# Controller_Rev_3.net
KiCad netlist of a schematic drawn in EAGLE
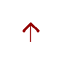
[diagram p0: schematic, sheet 1, part 1 of 3]
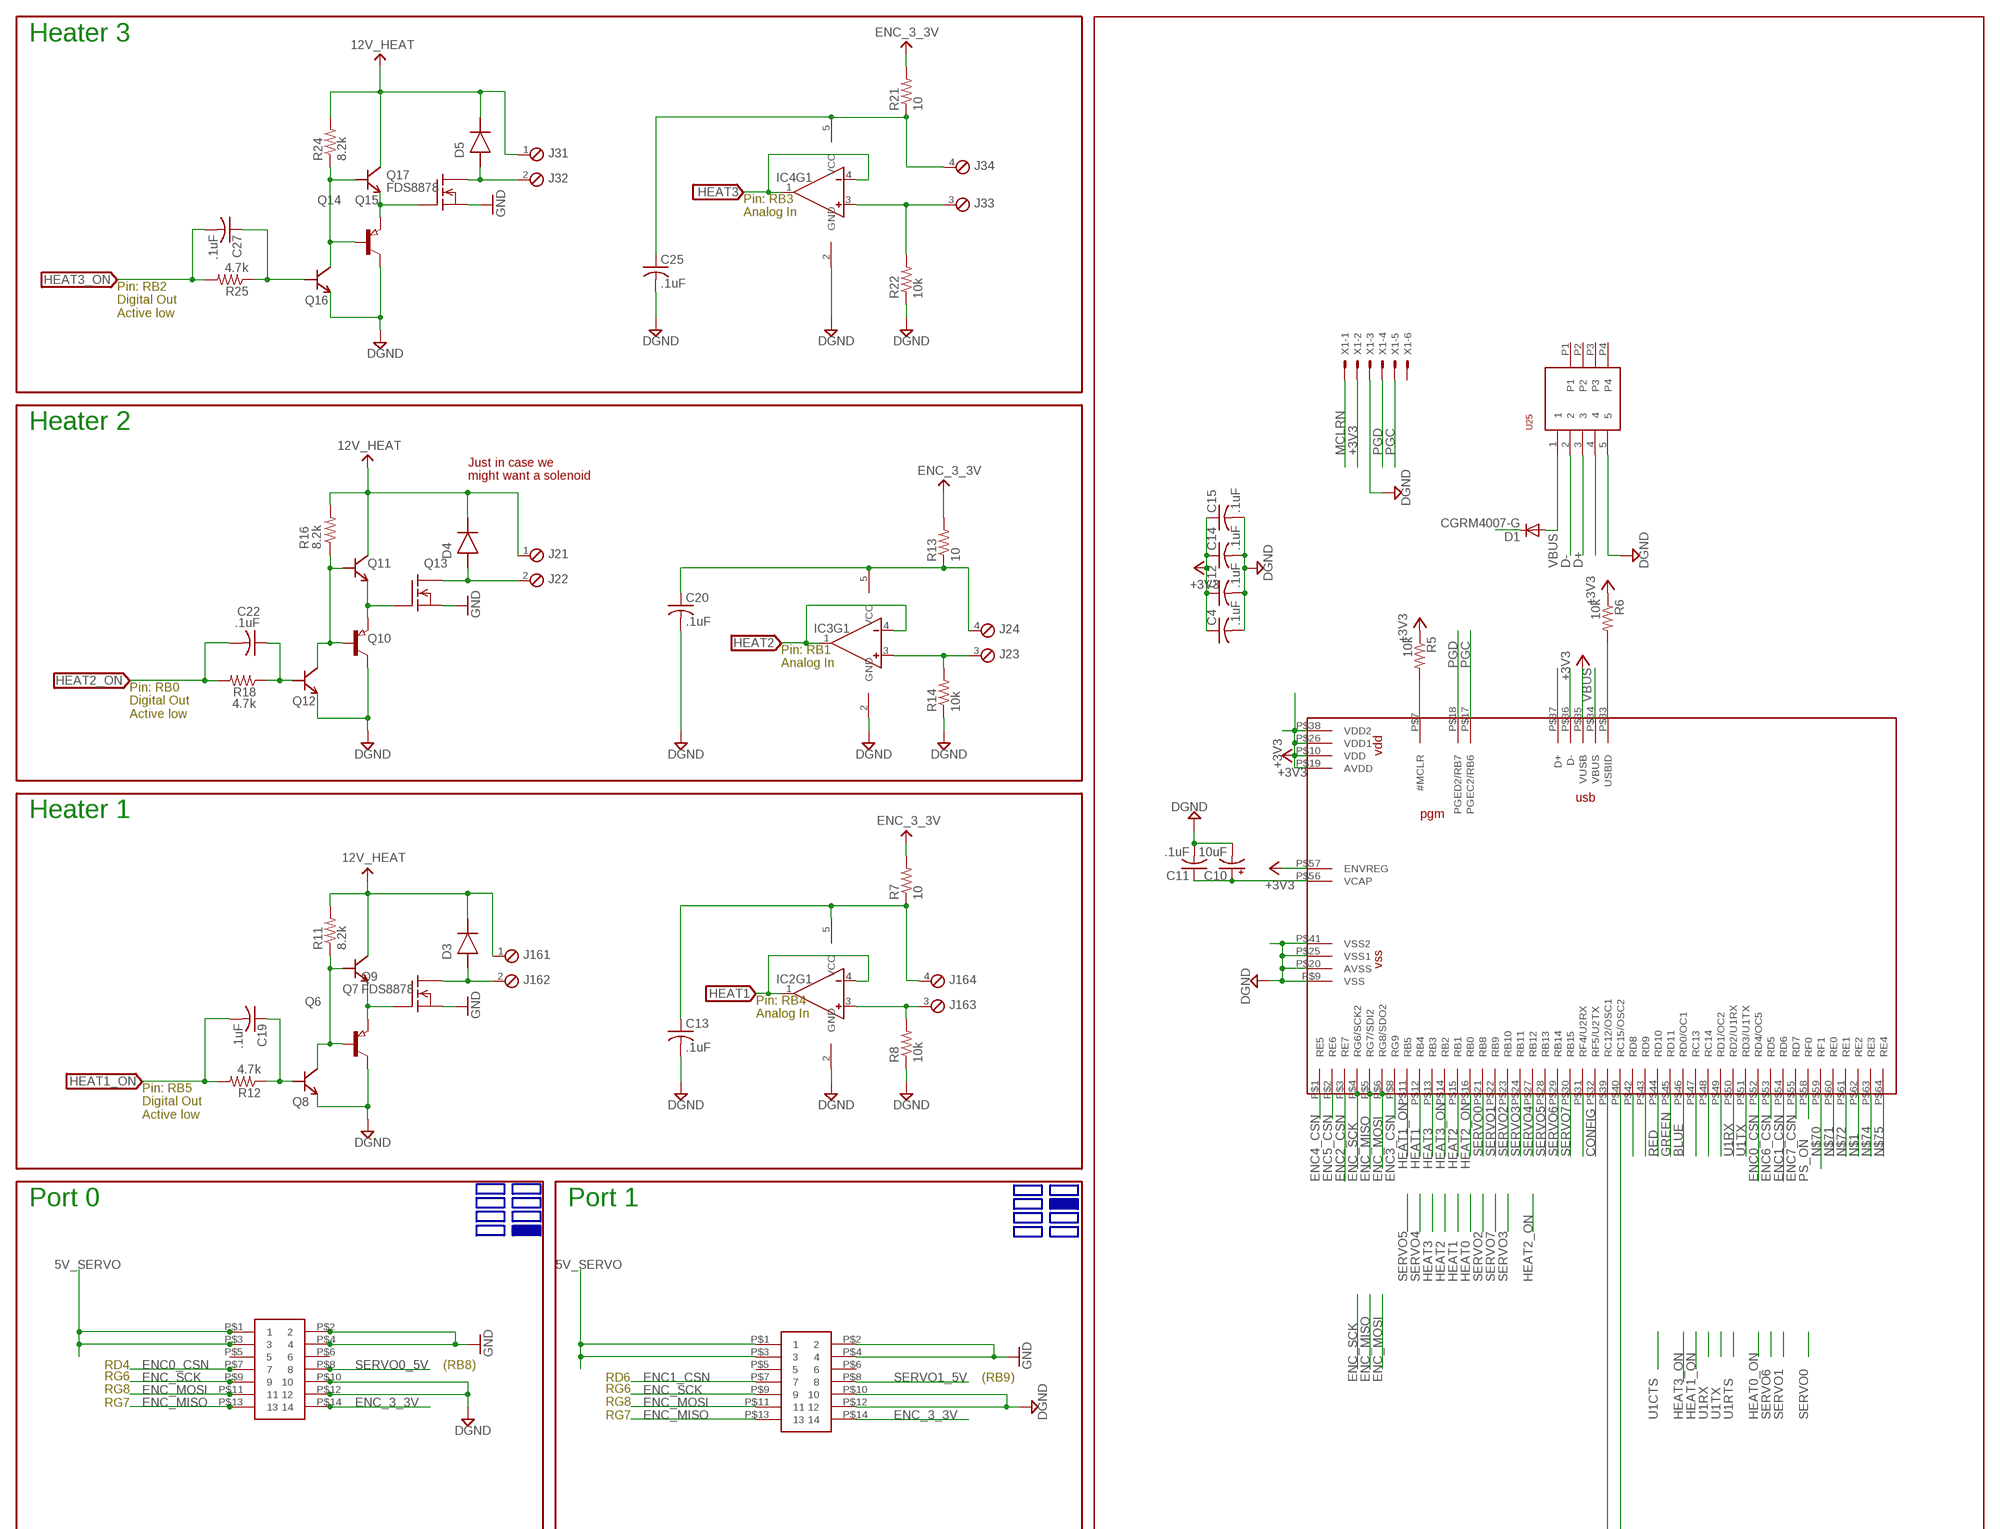
[diagram p1: schematic, sheet 1, part 2 of 3]
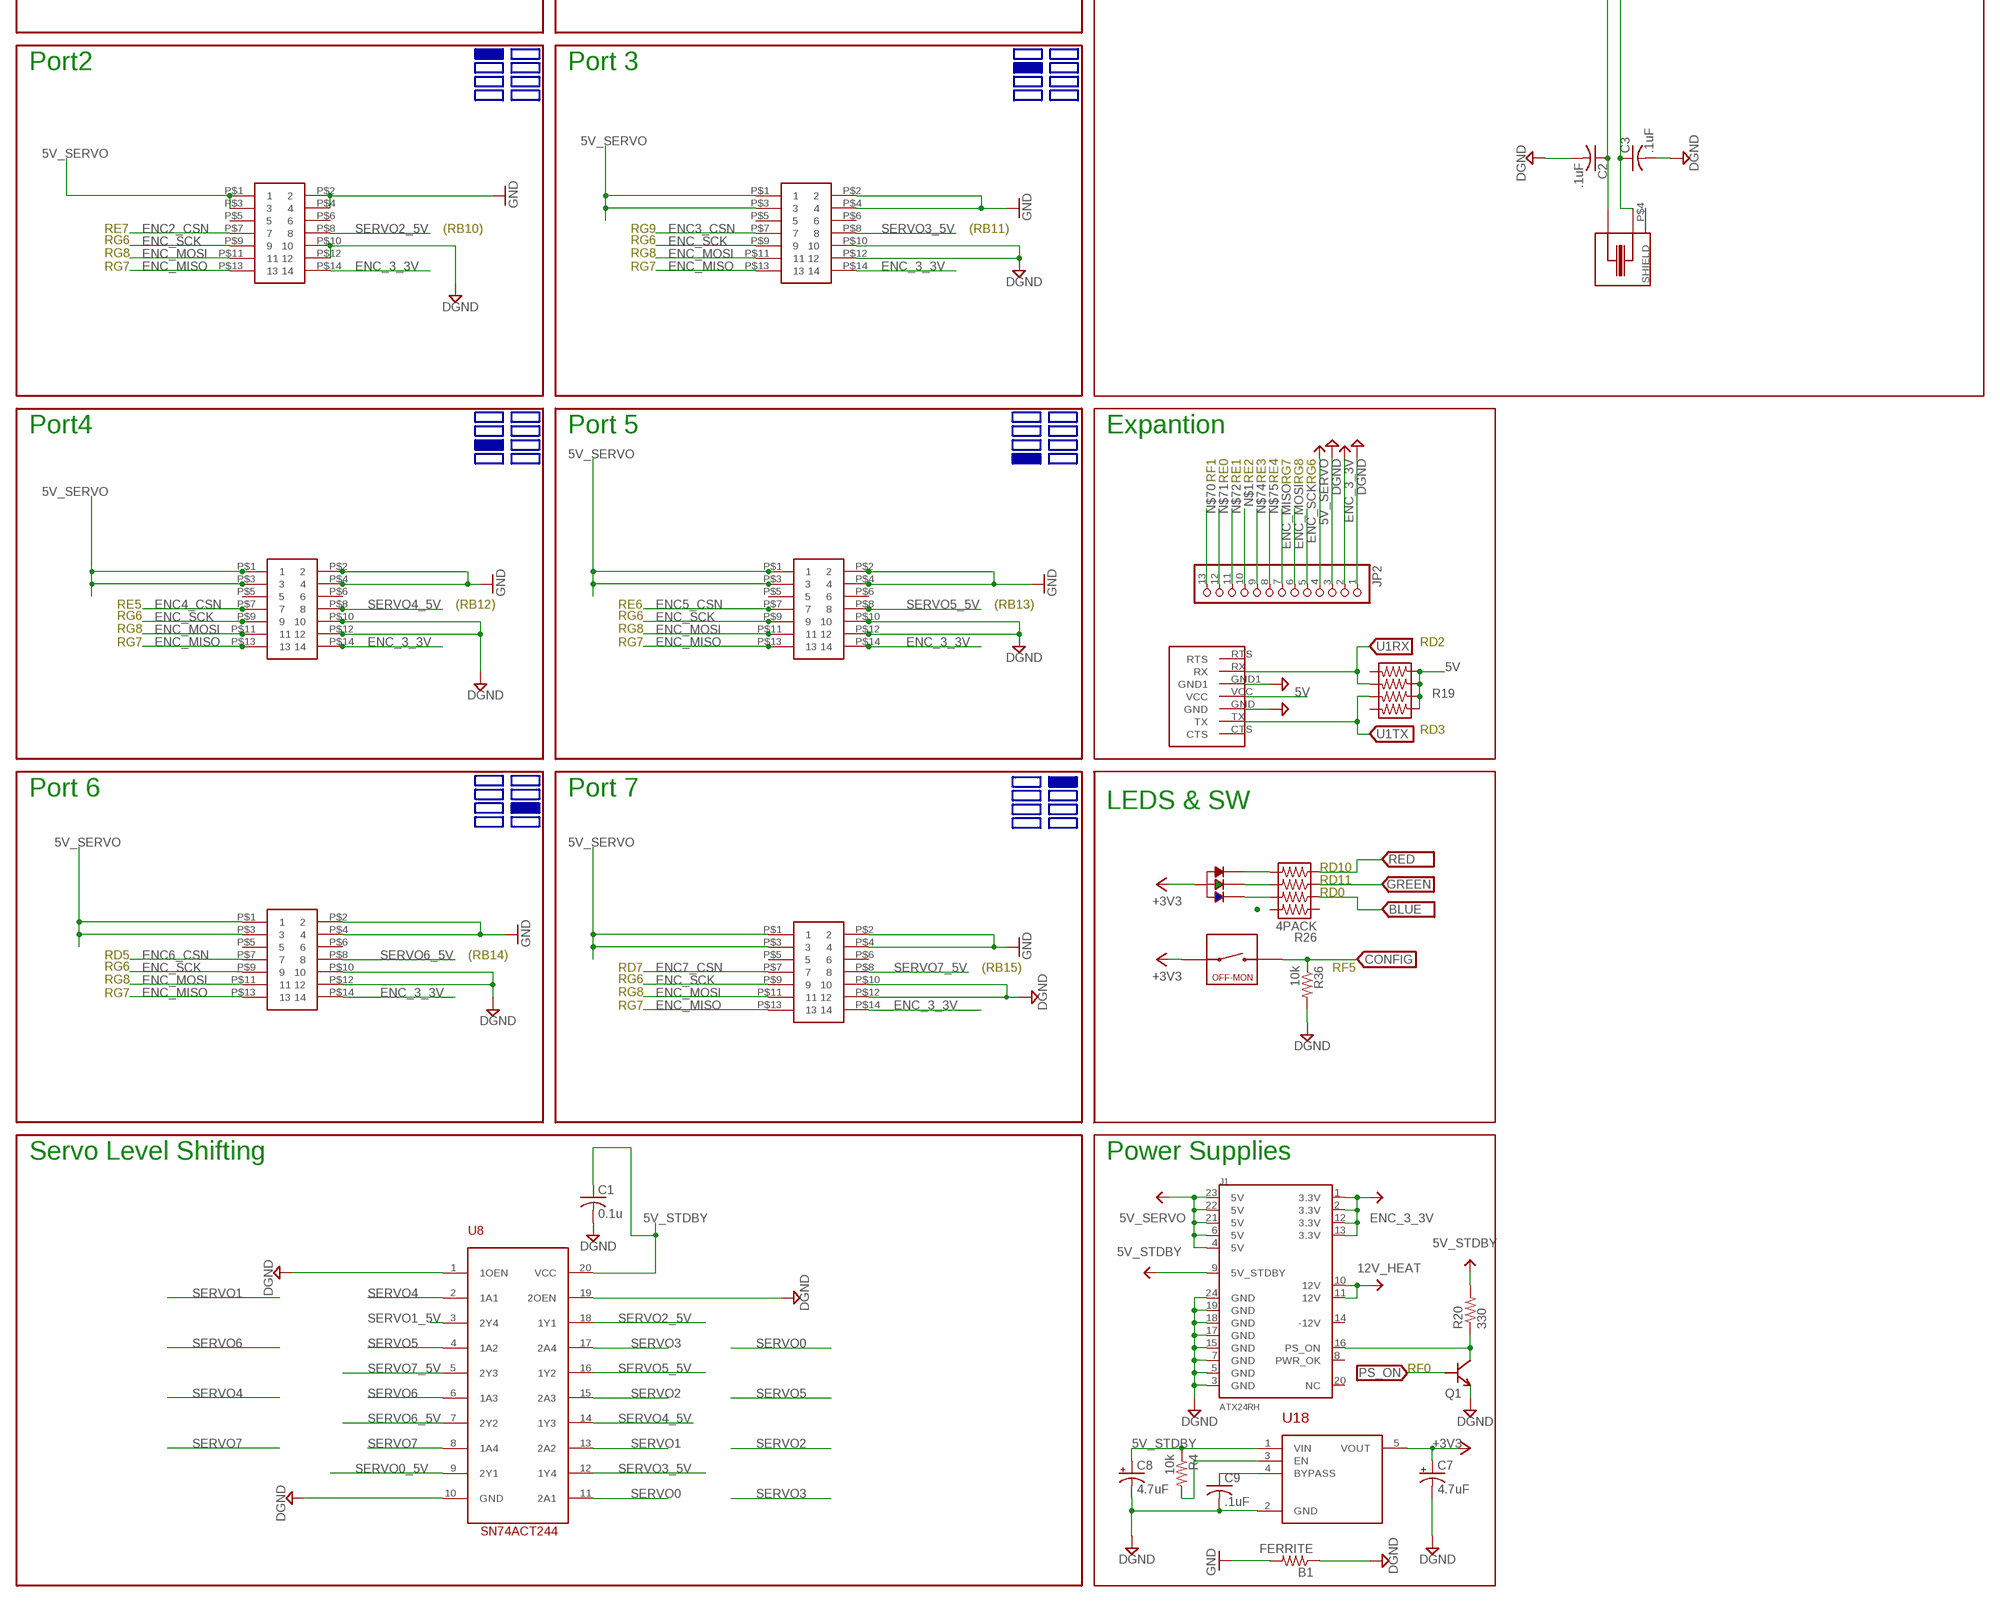
[diagram p2: schematic, sheet 1, part 3 of 3]

(export (version "E")
  (design (tool "Eeschema 10.0.6"))
  (components
    (comp (ref "B1")
      (value "FERRITE")
      (footprint "eagle-import:R0603")
      (libsource (lib "eagle-import") (part "R-US_R0603"))
    )
    (comp (ref "C1")
      (value "0.1u")
      (footprint "eagle-import:C0402")
      (libsource (lib "eagle-import") (part "resistor_C-USC0402"))
    )
    (comp (ref "C2")
      (value ".1uF")
      (footprint "eagle-import:C0603")
      (libsource (lib "eagle-import") (part "C-USC0603"))
    )
    (comp (ref "C3")
      (value ".1uF")
      (footprint "eagle-import:C0603")
      (libsource (lib "eagle-import") (part "C-USC0603"))
    )
    (comp (ref "C4")
      (value ".1uF")
      (footprint "eagle-import:C0603")
      (libsource (lib "eagle-import") (part "C-USC0603"))
    )
    (comp (ref "C7")
      (value "4.7uF")
      (footprint "eagle-import:R_2012-12R")
      (libsource (lib "eagle-import") (part "CPOL-USR/2012-12R"))
    )
    (comp (ref "C8")
      (value "4.7uF")
      (footprint "eagle-import:R_2012-12R")
      (libsource (lib "eagle-import") (part "CPOL-USR/2012-12R"))
    )
    (comp (ref "C9")
      (value ".1uF")
      (footprint "eagle-import:C0402")
      (libsource (lib "eagle-import") (part "C-USC0402"))
    )
    (comp (ref "C10")
      (value "10uF")
      (footprint "eagle-import:R_2012-12R")
      (libsource (lib "eagle-import") (part "CPOL-USR/2012-12R"))
    )
    (comp (ref "C11")
      (value ".1uF")
      (footprint "eagle-import:C0603")
      (libsource (lib "eagle-import") (part "C-USC0603"))
    )
    (comp (ref "C12")
      (value ".1uF")
      (footprint "eagle-import:C0603")
      (libsource (lib "eagle-import") (part "C-USC0603"))
    )
    (comp (ref "C13")
      (value ".1uF")
      (footprint "eagle-import:C0603")
      (libsource (lib "eagle-import") (part "C-USC0603"))
    )
    (comp (ref "C14")
      (value ".1uF")
      (footprint "eagle-import:C0603")
      (libsource (lib "eagle-import") (part "C-USC0603"))
    )
    (comp (ref "C15")
      (value ".1uF")
      (footprint "eagle-import:C0603")
      (libsource (lib "eagle-import") (part "C-USC0603"))
    )
    (comp (ref "C19")
      (value ".1uF")
      (footprint "eagle-import:C0603")
      (libsource (lib "eagle-import") (part "C-USC0603"))
    )
    (comp (ref "C20")
      (value ".1uF")
      (footprint "eagle-import:C0603")
      (libsource (lib "eagle-import") (part "C-USC0603"))
    )
    (comp (ref "C22")
      (value ".1uF")
      (footprint "eagle-import:C0603")
      (libsource (lib "eagle-import") (part "C-USC0603"))
    )
    (comp (ref "C25")
      (value ".1uF")
      (footprint "eagle-import:C0603")
      (libsource (lib "eagle-import") (part "C-USC0603"))
    )
    (comp (ref "C27")
      (value ".1uF")
      (footprint "eagle-import:C0603")
      (libsource (lib "eagle-import") (part "C-USC0603"))
    )
    (comp (ref "D1")
      (value "CGRM4007-G")
      (footprint "eagle-import:SOD-123_MINI-SMA")
      (libsource (lib "eagle-import") (part "CGRM400-G7"))
    )
    (comp (ref "D3")
      (value "DISCRETE_DIODESMA")
      (footprint "eagle-import:DISCRETE_SMA")
      (libsource (lib "eagle-import") (part "DISCRETE_DIODESMA"))
    )
    (comp (ref "D4")
      (value "DISCRETE_DIODESMA")
      (footprint "eagle-import:DISCRETE_SMA")
      (libsource (lib "eagle-import") (part "DISCRETE_DIODESMA"))
    )
    (comp (ref "D5")
      (value "DISCRETE_DIODESMA")
      (footprint "eagle-import:DISCRETE_SMA")
      (libsource (lib "eagle-import") (part "DISCRETE_DIODESMA"))
    )
    (comp (ref "IC2")
      (value "MICROCHIP_MCP6001-LT")
      (footprint "eagle-import:MICROCHIP_SC70-5-LT")
      (libsource (lib "eagle-import") (part "MICROCHIP_MCP6001-LT"))
    )
    (comp (ref "IC3")
      (value "MICROCHIP_MCP6001-LT")
      (footprint "eagle-import:MICROCHIP_SC70-5-LT")
      (libsource (lib "eagle-import") (part "MICROCHIP_MCP6001-LT"))
    )
    (comp (ref "IC4")
      (value "MICROCHIP_MCP6001-LT")
      (footprint "eagle-import:MICROCHIP_SC70-5-LT")
      (libsource (lib "eagle-import") (part "MICROCHIP_MCP6001-LT"))
    )
    (comp (ref "J1")
      (value "ATX24RH")
      (footprint "eagle-import:ATX24_RIGHT_ANGLE")
      (libsource (lib "eagle-import") (part "ATX24RH"))
    )
    (comp (ref "J2")
      (value "OSTVN04A150")
      (footprint "eagle-import:4POL254")
      (libsource (lib "eagle-import") (part "OSTVN04A150"))
    )
    (comp (ref "J3")
      (value "OSTVN04A150")
      (footprint "eagle-import:4POL254")
      (libsource (lib "eagle-import") (part "OSTVN04A150"))
    )
    (comp (ref "J10")
      (value "WASP7PIN")
      (footprint "eagle-import:WASP7PIN")
      (libsource (lib "eagle-import") (part "WASP7PIN"))
    )
    (comp (ref "J16")
      (value "OSTVN04A150")
      (footprint "eagle-import:4POL254")
      (libsource (lib "eagle-import") (part "OSTVN04A150"))
    )
    (comp (ref "JP2")
      (value "PINHD-1X13_BIG")
      (footprint "eagle-import:1X13-BIG")
      (libsource (lib "eagle-import") (part "PINHD-1X13_BIG"))
    )
    (comp (ref "Q1")
      (value "DISCRETE_MMBT3904LT1G")
      (footprint "eagle-import:DISCRETE_SOT23")
      (libsource (lib "eagle-import") (part "DISCRETE_MMBT3904LT1G"))
    )
    (comp (ref "Q6")
      (value "PNP-TRANSISTOR_SOT23")
      (footprint "eagle-import:SOT23")
      (libsource (lib "eagle-import") (part "PNP-TRANSISTOR_SOT23"))
    )
    (comp (ref "Q7")
      (value "DISCRETE_MMBT3904LT1G")
      (footprint "eagle-import:DISCRETE_SOT23")
      (libsource (lib "eagle-import") (part "DISCRETE_MMBT3904LT1G"))
    )
    (comp (ref "Q8")
      (value "DISCRETE_MMBT3904LT1G")
      (footprint "eagle-import:DISCRETE_SOT23")
      (libsource (lib "eagle-import") (part "DISCRETE_MMBT3904LT1G"))
    )
    (comp (ref "Q9")
      (value "FDS8878")
      (footprint "eagle-import:SO-8")
      (libsource (lib "eagle-import") (part "FDS5680"))
    )
    (comp (ref "Q10")
      (value "PNP-TRANSISTOR_SOT23")
      (footprint "eagle-import:SOT23")
      (libsource (lib "eagle-import") (part "PNP-TRANSISTOR_SOT23"))
    )
    (comp (ref "Q11")
      (value "DISCRETE_MMBT3904LT1G")
      (footprint "eagle-import:DISCRETE_SOT23")
      (libsource (lib "eagle-import") (part "DISCRETE_MMBT3904LT1G"))
    )
    (comp (ref "Q12")
      (value "DISCRETE_MMBT3904LT1G")
      (footprint "eagle-import:DISCRETE_SOT23")
      (libsource (lib "eagle-import") (part "DISCRETE_MMBT3904LT1G"))
    )
    (comp (ref "Q13")
      (value "FDS8878")
      (footprint "eagle-import:SO-8")
      (libsource (lib "eagle-import") (part "FDS5680"))
    )
    (comp (ref "Q14")
      (value "PNP-TRANSISTOR_SOT23")
      (footprint "eagle-import:SOT23")
      (libsource (lib "eagle-import") (part "PNP-TRANSISTOR_SOT23"))
    )
    (comp (ref "Q15")
      (value "DISCRETE_MMBT3904LT1G")
      (footprint "eagle-import:DISCRETE_SOT23")
      (libsource (lib "eagle-import") (part "DISCRETE_MMBT3904LT1G"))
    )
    (comp (ref "Q16")
      (value "DISCRETE_MMBT3904LT1G")
      (footprint "eagle-import:DISCRETE_SOT23")
      (libsource (lib "eagle-import") (part "DISCRETE_MMBT3904LT1G"))
    )
    (comp (ref "Q17")
      (value "FDS8878")
      (footprint "eagle-import:SO-8")
      (libsource (lib "eagle-import") (part "FDS5680"))
    )
    (comp (ref "R4")
      (value "10k")
      (footprint "eagle-import:R0402")
      (libsource (lib "eagle-import") (part "R-US_R0402"))
    )
    (comp (ref "R5")
      (value "10k")
      (footprint "eagle-import:R0603")
      (libsource (lib "eagle-import") (part "R-US_R0603"))
    )
    (comp (ref "R6")
      (value "10k")
      (footprint "eagle-import:R0603")
      (libsource (lib "eagle-import") (part "R-US_R0603"))
    )
    (comp (ref "R7")
      (value "10")
      (footprint "eagle-import:R0603")
      (libsource (lib "eagle-import") (part "R-US_R0603"))
    )
    (comp (ref "R8")
      (value "10k")
      (footprint "eagle-import:R0603")
      (libsource (lib "eagle-import") (part "R-US_R0603"))
    )
    (comp (ref "R11")
      (value "8.2k")
      (footprint "eagle-import:R0603")
      (libsource (lib "eagle-import") (part "R-US_R0603"))
    )
    (comp (ref "R12")
      (value "4.7k")
      (footprint "eagle-import:R0603")
      (libsource (lib "eagle-import") (part "R-US_R0603"))
    )
    (comp (ref "R13")
      (value "10")
      (footprint "eagle-import:R0603")
      (libsource (lib "eagle-import") (part "R-US_R0603"))
    )
    (comp (ref "R14")
      (value "10k")
      (footprint "eagle-import:R0603")
      (libsource (lib "eagle-import") (part "R-US_R0603"))
    )
    (comp (ref "R16")
      (value "8.2k")
      (footprint "eagle-import:R0603")
      (libsource (lib "eagle-import") (part "R-US_R0603"))
    )
    (comp (ref "R18")
      (value "4.7k")
      (footprint "eagle-import:R0603")
      (libsource (lib "eagle-import") (part "R-US_R0603"))
    )
    (comp (ref "R19")
      (value "4PACK")
      (footprint "eagle-import:4PACK_0603")
      (libsource (lib "eagle-import") (part "4PACK"))
    )
    (comp (ref "R20")
      (value "330")
      (footprint "eagle-import:R0603")
      (libsource (lib "eagle-import") (part "R-US_R0603"))
    )
    (comp (ref "R21")
      (value "10")
      (footprint "eagle-import:R0603")
      (libsource (lib "eagle-import") (part "R-US_R0603"))
    )
    (comp (ref "R22")
      (value "10k")
      (footprint "eagle-import:R0603")
      (libsource (lib "eagle-import") (part "R-US_R0603"))
    )
    (comp (ref "R24")
      (value "8.2k")
      (footprint "eagle-import:R0603")
      (libsource (lib "eagle-import") (part "R-US_R0603"))
    )
    (comp (ref "R25")
      (value "4.7k")
      (footprint "eagle-import:R0603")
      (libsource (lib "eagle-import") (part "R-US_R0603"))
    )
    (comp (ref "R26")
      (value "4PACK")
      (footprint "eagle-import:4PACK_0603")
      (libsource (lib "eagle-import") (part "4PACK"))
    )
    (comp (ref "R36")
      (value "10k")
      (footprint "eagle-import:R0603")
      (libsource (lib "eagle-import") (part "R-US_R0603"))
    )
    (comp (ref "SW3")
      (value "SPST")
      (footprint "eagle-import:B3U-1000P")
      (libsource (lib "eagle-import") (part "SPST"))
    )
    (comp (ref "U$1")
      (value "SBH11-NBPC-D07-SM-BK")
      (footprint "eagle-import:SBH11-NBPC-D07-SM-BK")
      (libsource (lib "eagle-import") (part "SBH11-NBPC-D07-SM-BK"))
    )
    (comp (ref "U$2")
      (value "SBH11-NBPC-D07-SM-BK")
      (footprint "eagle-import:SBH11-NBPC-D07-SM-BK")
      (libsource (lib "eagle-import") (part "SBH11-NBPC-D07-SM-BK"))
    )
    (comp (ref "U$3")
      (value "SBH11-NBPC-D07-SM-BK")
      (footprint "eagle-import:SBH11-NBPC-D07-SM-BK")
      (libsource (lib "eagle-import") (part "SBH11-NBPC-D07-SM-BK"))
    )
    (comp (ref "U$4")
      (value "SBH11-NBPC-D07-SM-BK")
      (footprint "eagle-import:SBH11-NBPC-D07-SM-BK")
      (libsource (lib "eagle-import") (part "SBH11-NBPC-D07-SM-BK"))
    )
    (comp (ref "U$5")
      (value "SBH11-NBPC-D07-SM-BK")
      (footprint "eagle-import:SBH11-NBPC-D07-SM-BK")
      (libsource (lib "eagle-import") (part "SBH11-NBPC-D07-SM-BK"))
    )
    (comp (ref "U$6")
      (value "SBH11-NBPC-D07-SM-BK")
      (footprint "eagle-import:SBH11-NBPC-D07-SM-BK")
      (libsource (lib "eagle-import") (part "SBH11-NBPC-D07-SM-BK"))
    )
    (comp (ref "U$7")
      (value "SBH11-NBPC-D07-SM-BK")
      (footprint "eagle-import:SBH11-NBPC-D07-SM-BK")
      (libsource (lib "eagle-import") (part "SBH11-NBPC-D07-SM-BK"))
    )
    (comp (ref "U$8")
      (value "SBH11-NBPC-D07-SM-BK")
      (footprint "eagle-import:SBH11-NBPC-D07-SM-BK")
      (libsource (lib "eagle-import") (part "SBH11-NBPC-D07-SM-BK"))
    )
    (comp (ref "U1")
      (value "TRI-LED-SMD")
      (footprint "eagle-import:TRI_LED_SMD")
      (libsource (lib "eagle-import") (part "TRI-LED-SMD"))
    )
    (comp (ref "U3")
      (value "PIC32-64TQFP64-2")
      (footprint "eagle-import:TQFP64-2")
      (libsource (lib "eagle-import") (part "PIC32-64TQFP64-2"))
    )
    (comp (ref "U8")
      (value "SN74ACT244")
      (footprint "eagle-import:20-SOIC")
      (libsource (lib "eagle-import") (part "SN74ACT244"))
    )
    (comp (ref "U18")
      (value "LDS3985XX33")
      (footprint "eagle-import:SOT23-5")
      (libsource (lib "eagle-import") (part "LDS3985XX33"))
    )
    (comp (ref "U25")
      (value "1734035-1_USB")
      (footprint "eagle-import:1734035-1_1734035")
      (libsource (lib "eagle-import") (part "1734035-1_USB"))
    )
    (comp (ref "X1")
      (value "22-23-2061")
      (footprint "eagle-import:22-23-2061")
      (fields (field (name "MF") "MOLEX"))
      (libsource (lib "eagle-import") (part "22-23-2061"))
    )
    (comp (ref "X2")
      (value "CMR3XXT")
      (footprint "eagle-import:CMR309T")
      (libsource (lib "eagle-import") (part "CMR3XXT"))
    )
  )
  (nets
    (net (code "2") (name "+3V3") (class "Default")
      (node (ref "C12") (pin "1") (pinfunction "1_1") (pintype "passive"))
      (node (ref "C14") (pin "1") (pinfunction "1_1") (pintype "passive"))
      (node (ref "C15") (pin "1") (pinfunction "1_1") (pintype "passive"))
      (node (ref "C4") (pin "1") (pinfunction "1_1") (pintype "passive"))
      (node (ref "C7") (pin "+") (pinfunction "+_+") (pintype "passive"))
      (node (ref "R5") (pin "1") (pinfunction "1_1") (pintype "passive"))
      (node (ref "R6") (pin "1") (pinfunction "1_1") (pintype "passive"))
      (node (ref "SW3") (pin "P$1") (pinfunction "P$1_P$1") (pintype "bidirectional"))
      (node (ref "U1") (pin "COMM-A") (pinfunction "COMM-A_COMM-A") (pintype "bidirectional"))
      (node (ref "U18") (pin "5") (pinfunction "VOUT_5") (pintype "bidirectional"))
      (node (ref "U3") (pin "P$10") (pinfunction "VDD_P$10") (pintype "bidirectional"))
      (node (ref "U3") (pin "P$19") (pinfunction "AVDD_P$19") (pintype "bidirectional"))
      (node (ref "U3") (pin "P$26") (pinfunction "VDD1_P$26") (pintype "bidirectional"))
      (node (ref "U3") (pin "P$35") (pinfunction "VUSB_P$35") (pintype "bidirectional"))
      (node (ref "U3") (pin "P$38") (pinfunction "VDD2_P$38") (pintype "bidirectional"))
      (node (ref "U3") (pin "P$57") (pinfunction "ENVREG_P$57") (pintype "bidirectional"))
      (node (ref "X1") (pin "2") (pinfunction "S_2") (pintype "passive"))
    )
    (net (code "3") (name "/5V") (class "Default")
      (node (ref "J10") (pin "VCC") (pinfunction "VCC_VCC") (pintype "bidirectional"))
      (node (ref "R19") (pin "R1B") (pinfunction "R1B_R1B") (pintype "passive"))
      (node (ref "R19") (pin "R2B") (pinfunction "R2B_R2B") (pintype "passive"))
      (node (ref "R19") (pin "R3B") (pinfunction "R3B_R3B") (pintype "passive"))
      (node (ref "R19") (pin "R4B") (pinfunction "R4B_R4B") (pintype "passive"))
    )
    (net (code "4") (name "/5V_SERVO") (class "Default")
      (node (ref "J1") (pin "21") (pinfunction "5V_21") (pintype "bidirectional"))
      (node (ref "J1") (pin "22") (pinfunction "5V_22") (pintype "bidirectional"))
      (node (ref "J1") (pin "23") (pinfunction "5V_23") (pintype "bidirectional"))
      (node (ref "J1") (pin "4") (pinfunction "5V_4") (pintype "bidirectional"))
      (node (ref "J1") (pin "6") (pinfunction "5V_6") (pintype "bidirectional"))
      (node (ref "JP2") (pin "4") (pinfunction "4_4") (pintype "passive"))
      (node (ref "U$1") (pin "P$1") (pinfunction "1_P$1") (pintype "bidirectional"))
      (node (ref "U$1") (pin "P$3") (pinfunction "3_P$3") (pintype "bidirectional"))
      (node (ref "U$2") (pin "P$1") (pinfunction "1_P$1") (pintype "bidirectional"))
      (node (ref "U$2") (pin "P$3") (pinfunction "3_P$3") (pintype "bidirectional"))
      (node (ref "U$3") (pin "P$1") (pinfunction "1_P$1") (pintype "bidirectional"))
      (node (ref "U$3") (pin "P$3") (pinfunction "3_P$3") (pintype "bidirectional"))
      (node (ref "U$4") (pin "P$1") (pinfunction "1_P$1") (pintype "bidirectional"))
      (node (ref "U$4") (pin "P$3") (pinfunction "3_P$3") (pintype "bidirectional"))
      (node (ref "U$5") (pin "P$1") (pinfunction "1_P$1") (pintype "bidirectional"))
      (node (ref "U$5") (pin "P$3") (pinfunction "3_P$3") (pintype "bidirectional"))
      (node (ref "U$6") (pin "P$1") (pinfunction "1_P$1") (pintype "bidirectional"))
      (node (ref "U$6") (pin "P$3") (pinfunction "3_P$3") (pintype "bidirectional"))
      (node (ref "U$7") (pin "P$1") (pinfunction "1_P$1") (pintype "bidirectional"))
      (node (ref "U$7") (pin "P$3") (pinfunction "3_P$3") (pintype "bidirectional"))
      (node (ref "U$8") (pin "P$1") (pinfunction "1_P$1") (pintype "bidirectional"))
      (node (ref "U$8") (pin "P$3") (pinfunction "3_P$3") (pintype "bidirectional"))
    )
    (net (code "5") (name "/5V_STDBY") (class "Default")
      (node (ref "C1") (pin "1") (pinfunction "1_1") (pintype "passive"))
      (node (ref "C8") (pin "+") (pinfunction "+_+") (pintype "passive"))
      (node (ref "D1") (pin "C") (pinfunction "C_C") (pintype "passive"))
      (node (ref "J1") (pin "9") (pinfunction "5V_STDBY_9") (pintype "bidirectional"))
      (node (ref "R20") (pin "2") (pinfunction "2_2") (pintype "passive"))
      (node (ref "R4") (pin "1") (pinfunction "1_1") (pintype "passive"))
      (node (ref "U18") (pin "1") (pinfunction "VIN_1") (pintype "bidirectional"))
      (node (ref "U8") (pin "20") (pinfunction "VCC_20") (pintype "bidirectional"))
    )
    (net (code "6") (name "/12V_HEAT") (class "Default")
      (node (ref "D3") (pin "C") (pinfunction "C_C") (pintype "bidirectional"))
      (node (ref "D4") (pin "C") (pinfunction "C_C") (pintype "bidirectional"))
      (node (ref "D5") (pin "C") (pinfunction "C_C") (pintype "bidirectional"))
      (node (ref "J1") (pin "10") (pinfunction "12V_10") (pintype "bidirectional"))
      (node (ref "J1") (pin "11") (pinfunction "12V_11") (pintype "bidirectional"))
      (node (ref "J16") (pin "1") (pinfunction "1_1") (pintype "passive"))
      (node (ref "J2") (pin "1") (pinfunction "1_1") (pintype "passive"))
      (node (ref "J3") (pin "1") (pinfunction "1_1") (pintype "passive"))
      (node (ref "Q11") (pin "3") (pinfunction "C_3") (pintype "bidirectional"))
      (node (ref "Q15") (pin "3") (pinfunction "C_3") (pintype "bidirectional"))
      (node (ref "Q7") (pin "3") (pinfunction "C_3") (pintype "bidirectional"))
      (node (ref "R11") (pin "2") (pinfunction "2_2") (pintype "passive"))
      (node (ref "R16") (pin "2") (pinfunction "2_2") (pintype "passive"))
      (node (ref "R24") (pin "2") (pinfunction "2_2") (pintype "passive"))
    )
    (net (code "7") (name "/BLUE") (class "Default")
      (node (ref "R26") (pin "R2B") (pinfunction "R2B_R2B") (pintype "passive"))
      (node (ref "U3") (pin "P$46") (pinfunction "RD0/OC1_P$46") (pintype "bidirectional"))
    )
    (net (code "8") (name "/CONFIG") (class "Default")
      (node (ref "R36") (pin "1") (pinfunction "1_1") (pintype "passive"))
      (node (ref "SW3") (pin "P$3") (pinfunction "P$2_P$3") (pintype "bidirectional"))
      (node (ref "U3") (pin "P$32") (pinfunction "RF5/U2TX_P$32") (pintype "bidirectional"))
    )
    (net (code "9") (name "/D+") (class "Default")
      (node (ref "U25") (pin "3") (pinfunction "3_3") (pintype "bidirectional"))
      (node (ref "U3") (pin "P$37") (pinfunction "D+_P$37") (pintype "bidirectional"))
    )
    (net (code "10") (name "/D-") (class "Default")
      (node (ref "U25") (pin "2") (pinfunction "2_2") (pintype "bidirectional"))
      (node (ref "U3") (pin "P$36") (pinfunction "D-_P$36") (pintype "bidirectional"))
    )
    (net (code "11") (name "/ENC0_CSN") (class "Default")
      (node (ref "U$8") (pin "P$7") (pinfunction "7_P$7") (pintype "bidirectional"))
      (node (ref "U3") (pin "P$52") (pinfunction "RD4/OC5_P$52") (pintype "bidirectional"))
    )
    (net (code "12") (name "/ENC1_CSN") (class "Default")
      (node (ref "U$6") (pin "P$7") (pinfunction "7_P$7") (pintype "bidirectional"))
      (node (ref "U3") (pin "P$54") (pinfunction "RD6_P$54") (pintype "bidirectional"))
    )
    (net (code "13") (name "/ENC2_CSN") (class "Default")
      (node (ref "U$1") (pin "P$7") (pinfunction "7_P$7") (pintype "bidirectional"))
      (node (ref "U3") (pin "P$3") (pinfunction "RE7_P$3") (pintype "bidirectional"))
    )
    (net (code "14") (name "/ENC3_CSN") (class "Default")
      (node (ref "U$2") (pin "P$7") (pinfunction "7_P$7") (pintype "bidirectional"))
      (node (ref "U3") (pin "P$8") (pinfunction "RG9_P$8") (pintype "bidirectional"))
    )
    (net (code "15") (name "/ENC4_CSN") (class "Default")
      (node (ref "U$3") (pin "P$7") (pinfunction "7_P$7") (pintype "bidirectional"))
      (node (ref "U3") (pin "P$1") (pinfunction "RE5_P$1") (pintype "bidirectional"))
    )
    (net (code "16") (name "/ENC5_CSN") (class "Default")
      (node (ref "U$4") (pin "P$7") (pinfunction "7_P$7") (pintype "bidirectional"))
      (node (ref "U3") (pin "P$2") (pinfunction "RE6_P$2") (pintype "bidirectional"))
    )
    (net (code "17") (name "/ENC6_CSN") (class "Default")
      (node (ref "U$7") (pin "P$7") (pinfunction "7_P$7") (pintype "bidirectional"))
      (node (ref "U3") (pin "P$53") (pinfunction "RD5_P$53") (pintype "bidirectional"))
    )
    (net (code "18") (name "/ENC7_CSN") (class "Default")
      (node (ref "U$5") (pin "P$7") (pinfunction "7_P$7") (pintype "bidirectional"))
      (node (ref "U3") (pin "P$55") (pinfunction "RD7_P$55") (pintype "bidirectional"))
    )
    (net (code "19") (name "/ENC_3_3V") (class "Default")
      (node (ref "J1") (pin "1") (pinfunction "3.3V_1") (pintype "bidirectional"))
      (node (ref "J1") (pin "12") (pinfunction "3.3V_12") (pintype "bidirectional"))
      (node (ref "J1") (pin "13") (pinfunction "3.3V_13") (pintype "bidirectional"))
      (node (ref "J1") (pin "2") (pinfunction "3.3V_2") (pintype "bidirectional"))
      (node (ref "JP2") (pin "2") (pinfunction "2_2") (pintype "passive"))
      (node (ref "R13") (pin "2") (pinfunction "2_2") (pintype "passive"))
      (node (ref "R21") (pin "2") (pinfunction "2_2") (pintype "passive"))
      (node (ref "R7") (pin "2") (pinfunction "2_2") (pintype "passive"))
      (node (ref "U$1") (pin "P$14") (pinfunction "14_P$14") (pintype "bidirectional"))
      (node (ref "U$2") (pin "P$14") (pinfunction "14_P$14") (pintype "bidirectional"))
      (node (ref "U$3") (pin "P$14") (pinfunction "14_P$14") (pintype "bidirectional"))
      (node (ref "U$4") (pin "P$14") (pinfunction "14_P$14") (pintype "bidirectional"))
      (node (ref "U$5") (pin "P$14") (pinfunction "14_P$14") (pintype "bidirectional"))
      (node (ref "U$6") (pin "P$14") (pinfunction "14_P$14") (pintype "bidirectional"))
      (node (ref "U$7") (pin "P$14") (pinfunction "14_P$14") (pintype "bidirectional"))
      (node (ref "U$8") (pin "P$14") (pinfunction "14_P$14") (pintype "bidirectional"))
    )
    (net (code "20") (name "/ENC_MISO") (class "Default")
      (node (ref "JP2") (pin "7") (pinfunction "7_7") (pintype "passive"))
      (node (ref "U$1") (pin "P$13") (pinfunction "13_P$13") (pintype "bidirectional"))
      (node (ref "U$2") (pin "P$13") (pinfunction "13_P$13") (pintype "bidirectional"))
      (node (ref "U$3") (pin "P$13") (pinfunction "13_P$13") (pintype "bidirectional"))
      (node (ref "U$4") (pin "P$13") (pinfunction "13_P$13") (pintype "bidirectional"))
      (node (ref "U$5") (pin "P$13") (pinfunction "13_P$13") (pintype "bidirectional"))
      (node (ref "U$6") (pin "P$13") (pinfunction "13_P$13") (pintype "bidirectional"))
      (node (ref "U$7") (pin "P$13") (pinfunction "13_P$13") (pintype "bidirectional"))
      (node (ref "U$8") (pin "P$13") (pinfunction "13_P$13") (pintype "bidirectional"))
      (node (ref "U3") (pin "P$5") (pinfunction "RG7/SDI2_P$5") (pintype "bidirectional"))
    )
    (net (code "21") (name "/ENC_MOSI") (class "Default")
      (node (ref "JP2") (pin "6") (pinfunction "6_6") (pintype "passive"))
      (node (ref "U$1") (pin "P$11") (pinfunction "11_P$11") (pintype "bidirectional"))
      (node (ref "U$2") (pin "P$11") (pinfunction "11_P$11") (pintype "bidirectional"))
      (node (ref "U$3") (pin "P$11") (pinfunction "11_P$11") (pintype "bidirectional"))
      (node (ref "U$4") (pin "P$11") (pinfunction "11_P$11") (pintype "bidirectional"))
      (node (ref "U$5") (pin "P$11") (pinfunction "11_P$11") (pintype "bidirectional"))
      (node (ref "U$6") (pin "P$11") (pinfunction "11_P$11") (pintype "bidirectional"))
      (node (ref "U$7") (pin "P$11") (pinfunction "11_P$11") (pintype "bidirectional"))
      (node (ref "U$8") (pin "P$11") (pinfunction "11_P$11") (pintype "bidirectional"))
      (node (ref "U3") (pin "P$6") (pinfunction "RG8/SDO2_P$6") (pintype "bidirectional"))
    )
    (net (code "22") (name "/ENC_SCK") (class "Default")
      (node (ref "JP2") (pin "5") (pinfunction "5_5") (pintype "passive"))
      (node (ref "U$1") (pin "P$9") (pinfunction "9_P$9") (pintype "bidirectional"))
      (node (ref "U$2") (pin "P$9") (pinfunction "9_P$9") (pintype "bidirectional"))
      (node (ref "U$3") (pin "P$9") (pinfunction "9_P$9") (pintype "bidirectional"))
      (node (ref "U$4") (pin "P$9") (pinfunction "9_P$9") (pintype "bidirectional"))
      (node (ref "U$5") (pin "P$9") (pinfunction "9_P$9") (pintype "bidirectional"))
      (node (ref "U$6") (pin "P$9") (pinfunction "9_P$9") (pintype "bidirectional"))
      (node (ref "U$7") (pin "P$9") (pinfunction "9_P$9") (pintype "bidirectional"))
      (node (ref "U$8") (pin "P$9") (pinfunction "9_P$9") (pintype "bidirectional"))
      (node (ref "U3") (pin "P$4") (pinfunction "RG6/SCK2_P$4") (pintype "bidirectional"))
    )
    (net (code "23") (name "/GREEN") (class "Default")
      (node (ref "R26") (pin "R3B") (pinfunction "R3B_R3B") (pintype "passive"))
      (node (ref "U3") (pin "P$45") (pinfunction "RD11_P$45") (pintype "bidirectional"))
    )
    (net (code "26") (name "/HEAT1") (class "Default")
      (node (ref "IC2") (pin "1") (pinfunction "OUT_1") (pintype "output"))
      (node (ref "IC2") (pin "4") (pinfunction "IN-_4") (pintype "input"))
      (node (ref "U3") (pin "P$12") (pinfunction "RB4_P$12") (pintype "bidirectional"))
    )
    (net (code "27") (name "/HEAT1_ON") (class "Default")
      (node (ref "C19") (pin "2") (pinfunction "2_2") (pintype "passive"))
      (node (ref "R12") (pin "2") (pinfunction "2_2") (pintype "passive"))
      (node (ref "U3") (pin "P$11") (pinfunction "RB5_P$11") (pintype "bidirectional"))
    )
    (net (code "28") (name "/HEAT2") (class "Default")
      (node (ref "IC3") (pin "1") (pinfunction "OUT_1") (pintype "output"))
      (node (ref "IC3") (pin "4") (pinfunction "IN-_4") (pintype "input"))
      (node (ref "U3") (pin "P$15") (pinfunction "RB1_P$15") (pintype "bidirectional"))
    )
    (net (code "29") (name "/HEAT2_ON") (class "Default")
      (node (ref "C22") (pin "2") (pinfunction "2_2") (pintype "passive"))
      (node (ref "R18") (pin "2") (pinfunction "2_2") (pintype "passive"))
      (node (ref "U3") (pin "P$16") (pinfunction "RB0_P$16") (pintype "bidirectional"))
    )
    (net (code "30") (name "/HEAT3") (class "Default")
      (node (ref "IC4") (pin "1") (pinfunction "OUT_1") (pintype "output"))
      (node (ref "IC4") (pin "4") (pinfunction "IN-_4") (pintype "input"))
      (node (ref "U3") (pin "P$13") (pinfunction "RB3_P$13") (pintype "bidirectional"))
    )
    (net (code "31") (name "/HEAT3_ON") (class "Default")
      (node (ref "C27") (pin "2") (pinfunction "2_2") (pintype "passive"))
      (node (ref "R25") (pin "2") (pinfunction "2_2") (pintype "passive"))
      (node (ref "U3") (pin "P$14") (pinfunction "RB2_P$14") (pintype "bidirectional"))
    )
    (net (code "32") (name "/MCLRN") (class "Default")
      (node (ref "R5") (pin "2") (pinfunction "2_2") (pintype "passive"))
      (node (ref "U3") (pin "P$7") (pinfunction "#MCLR_P$7") (pintype "bidirectional"))
      (node (ref "X1") (pin "1") (pinfunction "S_1") (pintype "passive"))
    )
    (net (code "33") (name "/N$1") (class "Default")
      (node (ref "JP2") (pin "10") (pinfunction "10_10") (pintype "passive"))
      (node (ref "U3") (pin "P$62") (pinfunction "RE2_P$62") (pintype "bidirectional"))
    )
    (net (code "34") (name "/N$70") (class "Default")
      (node (ref "JP2") (pin "13") (pinfunction "13_13") (pintype "passive"))
      (node (ref "U3") (pin "P$59") (pinfunction "RF1_P$59") (pintype "bidirectional"))
    )
    (net (code "35") (name "/N$71") (class "Default")
      (node (ref "JP2") (pin "12") (pinfunction "12_12") (pintype "passive"))
      (node (ref "U3") (pin "P$60") (pinfunction "RE0_P$60") (pintype "bidirectional"))
    )
    (net (code "36") (name "/N$72") (class "Default")
      (node (ref "JP2") (pin "11") (pinfunction "11_11") (pintype "passive"))
      (node (ref "U3") (pin "P$61") (pinfunction "RE1_P$61") (pintype "bidirectional"))
    )
    (net (code "37") (name "/N$74") (class "Default")
      (node (ref "JP2") (pin "9") (pinfunction "9_9") (pintype "passive"))
      (node (ref "U3") (pin "P$63") (pinfunction "RE3_P$63") (pintype "bidirectional"))
    )
    (net (code "38") (name "/N$75") (class "Default")
      (node (ref "JP2") (pin "8") (pinfunction "8_8") (pintype "passive"))
      (node (ref "U3") (pin "P$64") (pinfunction "RE4_P$64") (pintype "bidirectional"))
    )
    (net (code "39") (name "/PGC") (class "Default")
      (node (ref "U3") (pin "P$17") (pinfunction "PGEC2/RB6_P$17") (pintype "bidirectional"))
      (node (ref "X1") (pin "5") (pinfunction "S_5") (pintype "passive"))
    )
    (net (code "40") (name "/PGD") (class "Default")
      (node (ref "U3") (pin "P$18") (pinfunction "PGED2/RB7_P$18") (pintype "bidirectional"))
      (node (ref "X1") (pin "4") (pinfunction "S_4") (pintype "passive"))
    )
    (net (code "41") (name "/PS_ON") (class "Default")
      (node (ref "Q1") (pin "1") (pinfunction "B_1") (pintype "bidirectional"))
      (node (ref "U3") (pin "P$58") (pinfunction "RF0_P$58") (pintype "bidirectional"))
    )
    (net (code "42") (name "/RED") (class "Default")
      (node (ref "R26") (pin "R4B") (pinfunction "R4B_R4B") (pintype "passive"))
      (node (ref "U3") (pin "P$44") (pinfunction "RD10_P$44") (pintype "bidirectional"))
    )
    (net (code "43") (name "/SERVO0") (class "Default")
      (node (ref "U3") (pin "P$21") (pinfunction "RB8_P$21") (pintype "bidirectional"))
      (node (ref "U8") (pin "11") (pinfunction "2A1_11") (pintype "bidirectional"))
    )
    (net (code "44") (name "/SERVO0_5V") (class "Default")
      (node (ref "U$8") (pin "P$8") (pinfunction "8_P$8") (pintype "bidirectional"))
      (node (ref "U8") (pin "9") (pinfunction "2Y1_9") (pintype "bidirectional"))
    )
    (net (code "45") (name "/SERVO1") (class "Default")
      (node (ref "U3") (pin "P$22") (pinfunction "RB9_P$22") (pintype "bidirectional"))
      (node (ref "U8") (pin "13") (pinfunction "2A2_13") (pintype "bidirectional"))
    )
    (net (code "46") (name "/SERVO1_5V") (class "Default")
      (node (ref "U$6") (pin "P$8") (pinfunction "8_P$8") (pintype "bidirectional"))
      (node (ref "U8") (pin "3") (pinfunction "2Y4_3") (pintype "bidirectional"))
    )
    (net (code "47") (name "/SERVO2") (class "Default")
      (node (ref "U3") (pin "P$23") (pinfunction "RB10_P$23") (pintype "bidirectional"))
      (node (ref "U8") (pin "15") (pinfunction "2A3_15") (pintype "bidirectional"))
    )
    (net (code "48") (name "/SERVO2_5V") (class "Default")
      (node (ref "U$1") (pin "P$8") (pinfunction "8_P$8") (pintype "bidirectional"))
      (node (ref "U8") (pin "18") (pinfunction "1Y1_18") (pintype "bidirectional"))
    )
    (net (code "49") (name "/SERVO3") (class "Default")
      (node (ref "U3") (pin "P$24") (pinfunction "RB11_P$24") (pintype "bidirectional"))
      (node (ref "U8") (pin "17") (pinfunction "2A4_17") (pintype "bidirectional"))
    )
    (net (code "50") (name "/SERVO3_5V") (class "Default")
      (node (ref "U$2") (pin "P$8") (pinfunction "8_P$8") (pintype "bidirectional"))
      (node (ref "U8") (pin "12") (pinfunction "1Y4_12") (pintype "bidirectional"))
    )
    (net (code "51") (name "/SERVO4") (class "Default")
      (node (ref "U3") (pin "P$27") (pinfunction "RB12_P$27") (pintype "bidirectional"))
      (node (ref "U8") (pin "2") (pinfunction "1A1_2") (pintype "bidirectional"))
    )
    (net (code "52") (name "/SERVO4_5V") (class "Default")
      (node (ref "U$3") (pin "P$8") (pinfunction "8_P$8") (pintype "bidirectional"))
      (node (ref "U8") (pin "14") (pinfunction "1Y3_14") (pintype "bidirectional"))
    )
    (net (code "53") (name "/SERVO5") (class "Default")
      (node (ref "U3") (pin "P$28") (pinfunction "RB13_P$28") (pintype "bidirectional"))
      (node (ref "U8") (pin "4") (pinfunction "1A2_4") (pintype "bidirectional"))
    )
    (net (code "54") (name "/SERVO5_5V") (class "Default")
      (node (ref "U$4") (pin "P$8") (pinfunction "8_P$8") (pintype "bidirectional"))
      (node (ref "U8") (pin "16") (pinfunction "1Y2_16") (pintype "bidirectional"))
    )
    (net (code "55") (name "/SERVO6") (class "Default")
      (node (ref "U3") (pin "P$29") (pinfunction "RB14_P$29") (pintype "bidirectional"))
      (node (ref "U8") (pin "6") (pinfunction "1A3_6") (pintype "bidirectional"))
    )
    (net (code "56") (name "/SERVO6_5V") (class "Default")
      (node (ref "U$7") (pin "P$8") (pinfunction "8_P$8") (pintype "bidirectional"))
      (node (ref "U8") (pin "7") (pinfunction "2Y2_7") (pintype "bidirectional"))
    )
    (net (code "57") (name "/SERVO7") (class "Default")
      (node (ref "U3") (pin "P$30") (pinfunction "RB15_P$30") (pintype "bidirectional"))
      (node (ref "U8") (pin "8") (pinfunction "1A4_8") (pintype "bidirectional"))
    )
    (net (code "58") (name "/SERVO7_5V") (class "Default")
      (node (ref "U$5") (pin "P$8") (pinfunction "8_P$8") (pintype "bidirectional"))
      (node (ref "U8") (pin "5") (pinfunction "2Y3_5") (pintype "bidirectional"))
    )
    (net (code "61") (name "/U1RX") (class "Default")
      (node (ref "J10") (pin "RX") (pinfunction "RX_RX") (pintype "bidirectional"))
      (node (ref "R19") (pin "R2A") (pinfunction "R2A_R2A") (pintype "passive"))
      (node (ref "U3") (pin "P$50") (pinfunction "RD2/U1RX_P$50") (pintype "bidirectional"))
    )
    (net (code "62") (name "/U1TX") (class "Default")
      (node (ref "J10") (pin "TX") (pinfunction "TX_TX") (pintype "bidirectional"))
      (node (ref "R19") (pin "R3A") (pinfunction "R3A_R3A") (pintype "passive"))
      (node (ref "U3") (pin "P$51") (pinfunction "RD3/U1TX_P$51") (pintype "bidirectional"))
    )
    (net (code "63") (name "/USBID") (class "Default")
      (node (ref "R6") (pin "2") (pinfunction "2_2") (pintype "passive"))
      (node (ref "U25") (pin "4") (pinfunction "4_4") (pintype "bidirectional"))
      (node (ref "U3") (pin "P$33") (pinfunction "USBID_P$33") (pintype "bidirectional"))
    )
    (net (code "64") (name "/VBUS") (class "Default")
      (node (ref "D1") (pin "A") (pinfunction "A_A") (pintype "passive"))
      (node (ref "U25") (pin "1") (pinfunction "1_1") (pintype "bidirectional"))
      (node (ref "U3") (pin "P$34") (pinfunction "VBUS_P$34") (pintype "bidirectional"))
    )
    (net (code "66") (name "DGND") (class "Default")
      (node (ref "B1") (pin "1") (pinfunction "1_1") (pintype "passive"))
      (node (ref "C1") (pin "2") (pinfunction "2_2") (pintype "passive"))
      (node (ref "C10") (pin "-") (pinfunction "-_-") (pintype "passive"))
      (node (ref "C11") (pin "2") (pinfunction "2_2") (pintype "passive"))
      (node (ref "C12") (pin "2") (pinfunction "2_2") (pintype "passive"))
      (node (ref "C13") (pin "2") (pinfunction "2_2") (pintype "passive"))
      (node (ref "C14") (pin "2") (pinfunction "2_2") (pintype "passive"))
      (node (ref "C15") (pin "2") (pinfunction "2_2") (pintype "passive"))
      (node (ref "C2") (pin "2") (pinfunction "2_2") (pintype "passive"))
      (node (ref "C20") (pin "2") (pinfunction "2_2") (pintype "passive"))
      (node (ref "C25") (pin "2") (pinfunction "2_2") (pintype "passive"))
      (node (ref "C3") (pin "2") (pinfunction "2_2") (pintype "passive"))
      (node (ref "C4") (pin "2") (pinfunction "2_2") (pintype "passive"))
      (node (ref "C7") (pin "-") (pinfunction "-_-") (pintype "passive"))
      (node (ref "C8") (pin "-") (pinfunction "-_-") (pintype "passive"))
      (node (ref "C9") (pin "2") (pinfunction "2_2") (pintype "passive"))
      (node (ref "IC2") (pin "2") (pinfunction "GND_2") (pintype "bidirectional"))
      (node (ref "IC3") (pin "2") (pinfunction "GND_2") (pintype "bidirectional"))
      (node (ref "IC4") (pin "2") (pinfunction "GND_2") (pintype "bidirectional"))
      (node (ref "J1") (pin "15") (pinfunction "GND_15") (pintype "bidirectional"))
      (node (ref "J1") (pin "17") (pinfunction "GND_17") (pintype "bidirectional"))
      (node (ref "J1") (pin "18") (pinfunction "GND_18") (pintype "bidirectional"))
      (node (ref "J1") (pin "19") (pinfunction "GND_19") (pintype "bidirectional"))
      (node (ref "J1") (pin "24") (pinfunction "GND_24") (pintype "bidirectional"))
      (node (ref "J1") (pin "3") (pinfunction "GND_3") (pintype "bidirectional"))
      (node (ref "J1") (pin "5") (pinfunction "GND_5") (pintype "bidirectional"))
      (node (ref "J1") (pin "7") (pinfunction "GND_7") (pintype "bidirectional"))
      (node (ref "J10") (pin "GND") (pinfunction "GND_GND") (pintype "bidirectional"))
      (node (ref "J10") (pin "GND1") (pinfunction "GND1_GND1") (pintype "bidirectional"))
      (node (ref "JP2") (pin "1") (pinfunction "1_1") (pintype "passive"))
      (node (ref "JP2") (pin "3") (pinfunction "3_3") (pintype "passive"))
      (node (ref "Q1") (pin "2") (pinfunction "E_2") (pintype "bidirectional"))
      (node (ref "Q10") (pin "3") (pinfunction "C_3") (pintype "passive"))
      (node (ref "Q12") (pin "2") (pinfunction "E_2") (pintype "bidirectional"))
      (node (ref "Q14") (pin "3") (pinfunction "C_3") (pintype "passive"))
      (node (ref "Q16") (pin "2") (pinfunction "E_2") (pintype "bidirectional"))
      (node (ref "Q6") (pin "3") (pinfunction "C_3") (pintype "passive"))
      (node (ref "Q8") (pin "2") (pinfunction "E_2") (pintype "bidirectional"))
      (node (ref "R14") (pin "1") (pinfunction "1_1") (pintype "passive"))
      (node (ref "R22") (pin "1") (pinfunction "1_1") (pintype "passive"))
      (node (ref "R36") (pin "2") (pinfunction "2_2") (pintype "passive"))
      (node (ref "R8") (pin "1") (pinfunction "1_1") (pintype "passive"))
      (node (ref "U$1") (pin "P$10") (pinfunction "10_P$10") (pintype "bidirectional"))
      (node (ref "U$1") (pin "P$12") (pinfunction "12_P$12") (pintype "bidirectional"))
      (node (ref "U$2") (pin "P$10") (pinfunction "10_P$10") (pintype "bidirectional"))
      (node (ref "U$2") (pin "P$12") (pinfunction "12_P$12") (pintype "bidirectional"))
      (node (ref "U$3") (pin "P$10") (pinfunction "10_P$10") (pintype "bidirectional"))
      (node (ref "U$3") (pin "P$12") (pinfunction "12_P$12") (pintype "bidirectional"))
      (node (ref "U$4") (pin "P$10") (pinfunction "10_P$10") (pintype "bidirectional"))
      (node (ref "U$4") (pin "P$12") (pinfunction "12_P$12") (pintype "bidirectional"))
      (node (ref "U$5") (pin "P$10") (pinfunction "10_P$10") (pintype "bidirectional"))
      (node (ref "U$5") (pin "P$12") (pinfunction "12_P$12") (pintype "bidirectional"))
      (node (ref "U$6") (pin "P$10") (pinfunction "10_P$10") (pintype "bidirectional"))
      (node (ref "U$6") (pin "P$12") (pinfunction "12_P$12") (pintype "bidirectional"))
      (node (ref "U$7") (pin "P$10") (pinfunction "10_P$10") (pintype "bidirectional"))
      (node (ref "U$7") (pin "P$12") (pinfunction "12_P$12") (pintype "bidirectional"))
      (node (ref "U$8") (pin "P$10") (pinfunction "10_P$10") (pintype "bidirectional"))
      (node (ref "U$8") (pin "P$12") (pinfunction "12_P$12") (pintype "bidirectional"))
      (node (ref "U18") (pin "2") (pinfunction "GND_2") (pintype "bidirectional"))
      (node (ref "U25") (pin "5") (pinfunction "5_5") (pintype "bidirectional"))
      (node (ref "U3") (pin "P$20") (pinfunction "AVSS_P$20") (pintype "bidirectional"))
      (node (ref "U3") (pin "P$25") (pinfunction "VSS1_P$25") (pintype "bidirectional"))
      (node (ref "U3") (pin "P$41") (pinfunction "VSS2_P$41") (pintype "bidirectional"))
      (node (ref "U3") (pin "P$9") (pinfunction "VSS_P$9") (pintype "bidirectional"))
      (node (ref "U8") (pin "1") (pinfunction "1OEN_1") (pintype "bidirectional"))
      (node (ref "U8") (pin "10") (pinfunction "GND_10") (pintype "bidirectional"))
      (node (ref "U8") (pin "19") (pinfunction "2OEN_19") (pintype "bidirectional"))
      (node (ref "X1") (pin "3") (pinfunction "S_3") (pintype "passive"))
    )
    (net (code "67") (name "GND") (class "Default")
      (node (ref "B1") (pin "2") (pinfunction "2_2") (pintype "passive"))
      (node (ref "Q13") (pin "1") (pinfunction "S_1") (pintype "passive"))
      (node (ref "Q13") (pin "2") (pinfunction "S_2") (pintype "passive"))
      (node (ref "Q13") (pin "3") (pinfunction "S_3") (pintype "passive"))
      (node (ref "Q17") (pin "1") (pinfunction "S_1") (pintype "passive"))
      (node (ref "Q17") (pin "2") (pinfunction "S_2") (pintype "passive"))
      (node (ref "Q17") (pin "3") (pinfunction "S_3") (pintype "passive"))
      (node (ref "Q9") (pin "1") (pinfunction "S_1") (pintype "passive"))
      (node (ref "Q9") (pin "2") (pinfunction "S_2") (pintype "passive"))
      (node (ref "Q9") (pin "3") (pinfunction "S_3") (pintype "passive"))
      (node (ref "U$1") (pin "P$2") (pinfunction "2_P$2") (pintype "bidirectional"))
      (node (ref "U$1") (pin "P$4") (pinfunction "4_P$4") (pintype "bidirectional"))
      (node (ref "U$2") (pin "P$2") (pinfunction "2_P$2") (pintype "bidirectional"))
      (node (ref "U$2") (pin "P$4") (pinfunction "4_P$4") (pintype "bidirectional"))
      (node (ref "U$3") (pin "P$2") (pinfunction "2_P$2") (pintype "bidirectional"))
      (node (ref "U$3") (pin "P$4") (pinfunction "4_P$4") (pintype "bidirectional"))
      (node (ref "U$4") (pin "P$2") (pinfunction "2_P$2") (pintype "bidirectional"))
      (node (ref "U$4") (pin "P$4") (pinfunction "4_P$4") (pintype "bidirectional"))
      (node (ref "U$5") (pin "P$2") (pinfunction "2_P$2") (pintype "bidirectional"))
      (node (ref "U$5") (pin "P$4") (pinfunction "4_P$4") (pintype "bidirectional"))
      (node (ref "U$6") (pin "P$2") (pinfunction "2_P$2") (pintype "bidirectional"))
      (node (ref "U$6") (pin "P$4") (pinfunction "4_P$4") (pintype "bidirectional"))
      (node (ref "U$7") (pin "P$2") (pinfunction "2_P$2") (pintype "bidirectional"))
      (node (ref "U$7") (pin "P$4") (pinfunction "4_P$4") (pintype "bidirectional"))
      (node (ref "U$8") (pin "P$2") (pinfunction "2_P$2") (pintype "bidirectional"))
      (node (ref "U$8") (pin "P$4") (pinfunction "4_P$4") (pintype "bidirectional"))
    )
    (net (code "68") (name "Net-(IC2A-IN+)") (class "Default")
      (node (ref "IC2") (pin "3") (pinfunction "IN+_3") (pintype "input"))
      (node (ref "J16") (pin "3") (pinfunction "1_3") (pintype "passive"))
      (node (ref "R8") (pin "2") (pinfunction "2_2") (pintype "passive"))
    )
    (net (code "69") (name "Net-(IC2B-VCC)") (class "Default")
      (node (ref "C13") (pin "1") (pinfunction "1_1") (pintype "passive"))
      (node (ref "IC2") (pin "5") (pinfunction "VCC_5") (pintype "bidirectional"))
      (node (ref "J16") (pin "4") (pinfunction "1_4") (pintype "passive"))
      (node (ref "R7") (pin "1") (pinfunction "1_1") (pintype "passive"))
    )
    (net (code "70") (name "Net-(IC3A-IN+)") (class "Default")
      (node (ref "IC3") (pin "3") (pinfunction "IN+_3") (pintype "input"))
      (node (ref "J2") (pin "3") (pinfunction "1_3") (pintype "passive"))
      (node (ref "R14") (pin "2") (pinfunction "2_2") (pintype "passive"))
    )
    (net (code "71") (name "Net-(IC3B-VCC)") (class "Default")
      (node (ref "C20") (pin "1") (pinfunction "1_1") (pintype "passive"))
      (node (ref "IC3") (pin "5") (pinfunction "VCC_5") (pintype "bidirectional"))
      (node (ref "J2") (pin "4") (pinfunction "1_4") (pintype "passive"))
      (node (ref "R13") (pin "1") (pinfunction "1_1") (pintype "passive"))
    )
    (net (code "72") (name "Net-(IC4A-IN+)") (class "Default")
      (node (ref "IC4") (pin "3") (pinfunction "IN+_3") (pintype "input"))
      (node (ref "J3") (pin "3") (pinfunction "1_3") (pintype "passive"))
      (node (ref "R22") (pin "2") (pinfunction "2_2") (pintype "passive"))
    )
    (net (code "73") (name "Net-(IC4B-VCC)") (class "Default")
      (node (ref "C25") (pin "1") (pinfunction "1_1") (pintype "passive"))
      (node (ref "IC4") (pin "5") (pinfunction "VCC_5") (pintype "bidirectional"))
      (node (ref "J3") (pin "4") (pinfunction "1_4") (pintype "passive"))
      (node (ref "R21") (pin "1") (pinfunction "1_1") (pintype "passive"))
    )
    (net (code "74") (name "Net-(J1-PS_ON)") (class "Default")
      (node (ref "J1") (pin "16") (pinfunction "PS_ON_16") (pintype "bidirectional"))
      (node (ref "Q1") (pin "3") (pinfunction "C_3") (pintype "bidirectional"))
      (node (ref "R20") (pin "1") (pinfunction "1_1") (pintype "passive"))
    )
    (net (code "75") (name "Net-(J2B-1)") (class "Default")
      (node (ref "D4") (pin "A") (pinfunction "A_A") (pintype "bidirectional"))
      (node (ref "J2") (pin "2") (pinfunction "1_2") (pintype "passive"))
      (node (ref "Q13") (pin "5") (pinfunction "D_5") (pintype "passive"))
      (node (ref "Q13") (pin "6") (pinfunction "D_6") (pintype "passive"))
      (node (ref "Q13") (pin "7") (pinfunction "D_7") (pintype "passive"))
      (node (ref "Q13") (pin "8") (pinfunction "D_8") (pintype "passive"))
    )
    (net (code "76") (name "Net-(J3B-1)") (class "Default")
      (node (ref "D5") (pin "A") (pinfunction "A_A") (pintype "bidirectional"))
      (node (ref "J3") (pin "2") (pinfunction "1_2") (pintype "passive"))
      (node (ref "Q17") (pin "5") (pinfunction "D_5") (pintype "passive"))
      (node (ref "Q17") (pin "6") (pinfunction "D_6") (pintype "passive"))
      (node (ref "Q17") (pin "7") (pinfunction "D_7") (pintype "passive"))
      (node (ref "Q17") (pin "8") (pinfunction "D_8") (pintype "passive"))
    )
    (net (code "77") (name "Net-(J16B-1)") (class "Default")
      (node (ref "D3") (pin "A") (pinfunction "A_A") (pintype "bidirectional"))
      (node (ref "J16") (pin "2") (pinfunction "1_2") (pintype "passive"))
      (node (ref "Q9") (pin "5") (pinfunction "D_5") (pintype "passive"))
      (node (ref "Q9") (pin "6") (pinfunction "D_6") (pintype "passive"))
      (node (ref "Q9") (pin "7") (pinfunction "D_7") (pintype "passive"))
      (node (ref "Q9") (pin "8") (pinfunction "D_8") (pintype "passive"))
    )
    (net (code "78") (name "Net-(Q6-B)") (class "Default")
      (node (ref "Q6") (pin "1") (pinfunction "B_1") (pintype "passive"))
      (node (ref "Q7") (pin "1") (pinfunction "B_1") (pintype "bidirectional"))
      (node (ref "Q8") (pin "3") (pinfunction "C_3") (pintype "bidirectional"))
      (node (ref "R11") (pin "1") (pinfunction "1_1") (pintype "passive"))
    )
    (net (code "79") (name "Net-(Q6-E)") (class "Default")
      (node (ref "Q6") (pin "2") (pinfunction "E_2") (pintype "passive"))
      (node (ref "Q7") (pin "2") (pinfunction "E_2") (pintype "bidirectional"))
      (node (ref "Q9") (pin "4") (pinfunction "G_4") (pintype "passive"))
    )
    (net (code "80") (name "Net-(Q8-B)") (class "Default")
      (node (ref "C19") (pin "1") (pinfunction "1_1") (pintype "passive"))
      (node (ref "Q8") (pin "1") (pinfunction "B_1") (pintype "bidirectional"))
      (node (ref "R12") (pin "1") (pinfunction "1_1") (pintype "passive"))
    )
    (net (code "81") (name "Net-(Q10-B)") (class "Default")
      (node (ref "Q10") (pin "1") (pinfunction "B_1") (pintype "passive"))
      (node (ref "Q11") (pin "1") (pinfunction "B_1") (pintype "bidirectional"))
      (node (ref "Q12") (pin "3") (pinfunction "C_3") (pintype "bidirectional"))
      (node (ref "R16") (pin "1") (pinfunction "1_1") (pintype "passive"))
    )
    (net (code "82") (name "Net-(Q10-E)") (class "Default")
      (node (ref "Q10") (pin "2") (pinfunction "E_2") (pintype "passive"))
      (node (ref "Q11") (pin "2") (pinfunction "E_2") (pintype "bidirectional"))
      (node (ref "Q13") (pin "4") (pinfunction "G_4") (pintype "passive"))
    )
    (net (code "83") (name "Net-(Q12-B)") (class "Default")
      (node (ref "C22") (pin "1") (pinfunction "1_1") (pintype "passive"))
      (node (ref "Q12") (pin "1") (pinfunction "B_1") (pintype "bidirectional"))
      (node (ref "R18") (pin "1") (pinfunction "1_1") (pintype "passive"))
    )
    (net (code "84") (name "Net-(Q14-B)") (class "Default")
      (node (ref "Q14") (pin "1") (pinfunction "B_1") (pintype "passive"))
      (node (ref "Q15") (pin "1") (pinfunction "B_1") (pintype "bidirectional"))
      (node (ref "Q16") (pin "3") (pinfunction "C_3") (pintype "bidirectional"))
      (node (ref "R24") (pin "1") (pinfunction "1_1") (pintype "passive"))
    )
    (net (code "85") (name "Net-(Q14-E)") (class "Default")
      (node (ref "Q14") (pin "2") (pinfunction "E_2") (pintype "passive"))
      (node (ref "Q15") (pin "2") (pinfunction "E_2") (pintype "bidirectional"))
      (node (ref "Q17") (pin "4") (pinfunction "G_4") (pintype "passive"))
    )
    (net (code "86") (name "Net-(Q16-B)") (class "Default")
      (node (ref "C27") (pin "1") (pinfunction "1_1") (pintype "passive"))
      (node (ref "Q16") (pin "1") (pinfunction "B_1") (pintype "bidirectional"))
      (node (ref "R25") (pin "1") (pinfunction "1_1") (pintype "passive"))
    )
    (net (code "87") (name "Net-(R26-PadR2A)") (class "Default")
      (node (ref "R26") (pin "R2A") (pinfunction "R2A_R2A") (pintype "passive"))
      (node (ref "U1") (pin "BLUE") (pinfunction "BLUE_BLUE") (pintype "bidirectional"))
    )
    (net (code "88") (name "Net-(R26-PadR3A)") (class "Default")
      (node (ref "R26") (pin "R3A") (pinfunction "R3A_R3A") (pintype "passive"))
      (node (ref "U1") (pin "GRN") (pinfunction "GRN_GRN") (pintype "bidirectional"))
    )
    (net (code "89") (name "Net-(R26-PadR4A)") (class "Default")
      (node (ref "R26") (pin "R4A") (pinfunction "R4A_R4A") (pintype "passive"))
      (node (ref "U1") (pin "RED") (pinfunction "RED_RED") (pintype "bidirectional"))
    )
    (net (code "90") (name "Net-(U3-RC12{slash}OSC1)") (class "Default")
      (node (ref "C2") (pin "1") (pinfunction "1_1") (pintype "passive"))
      (node (ref "U3") (pin "P$39") (pinfunction "RC12/OSC1_P$39") (pintype "bidirectional"))
      (node (ref "X2") (pin "P$1") (pinfunction "P$1_P$1") (pintype "bidirectional"))
    )
    (net (code "91") (name "Net-(U3-RC15{slash}OSC2)") (class "Default")
      (node (ref "C3") (pin "1") (pinfunction "1_1") (pintype "passive"))
      (node (ref "U3") (pin "P$40") (pinfunction "RC15/OSC2_P$40") (pintype "bidirectional"))
      (node (ref "X2") (pin "P$3") (pinfunction "P$2_P$3") (pintype "bidirectional"))
    )
    (net (code "92") (name "Net-(U3-VCAP)") (class "Default")
      (node (ref "C10") (pin "+") (pinfunction "+_+") (pintype "passive"))
      (node (ref "C11") (pin "1") (pinfunction "1_1") (pintype "passive"))
      (node (ref "U3") (pin "P$56") (pinfunction "VCAP_P$56") (pintype "bidirectional"))
    )
    (net (code "93") (name "Net-(U18-BYPASS)") (class "Default")
      (node (ref "C9") (pin "1") (pinfunction "1_1") (pintype "passive"))
      (node (ref "U18") (pin "4") (pinfunction "BYPASS_4") (pintype "bidirectional"))
    )
    (net (code "94") (name "Net-(U18-EN)") (class "Default")
      (node (ref "R4") (pin "2") (pinfunction "2_2") (pintype "passive"))
      (node (ref "U18") (pin "3") (pinfunction "EN_3") (pintype "bidirectional"))
    )
    (net (code "95") (name "unconnected-(J1--12V-Pad14)") (class "Default")
      (node (ref "J1") (pin "14") (pinfunction "-12V_14") (pintype "bidirectional"))
    )
    (net (code "96") (name "unconnected-(J1-NC-Pad20)") (class "Default")
      (node (ref "J1") (pin "20") (pinfunction "NC_20") (pintype "bidirectional"))
    )
    (net (code "97") (name "unconnected-(J1-PWR_OK-Pad8)") (class "Default")
      (node (ref "J1") (pin "8") (pinfunction "PWR_OK_8") (pintype "bidirectional"))
    )
    (net (code "98") (name "unconnected-(J10-PadCTS)") (class "Default")
      (node (ref "J10") (pin "CTS") (pinfunction "CTS_CTS") (pintype "bidirectional"))
    )
    (net (code "99") (name "unconnected-(J10-PadRTS)") (class "Default")
      (node (ref "J10") (pin "RTS") (pinfunction "RTS_RTS") (pintype "bidirectional"))
    )
    (net (code "100") (name "unconnected-(R19-PadR1A)") (class "Default")
      (node (ref "R19") (pin "R1A") (pinfunction "R1A_R1A") (pintype "passive"))
    )
    (net (code "101") (name "unconnected-(R19-PadR4A)") (class "Default")
      (node (ref "R19") (pin "R4A") (pinfunction "R4A_R4A") (pintype "passive"))
    )
    (net (code "102") (name "unconnected-(R26-PadR1A)") (class "Default")
      (node (ref "R26") (pin "R1A") (pinfunction "R1A_R1A") (pintype "passive"))
    )
    (net (code "103") (name "unconnected-(R26-PadR1B)") (class "Default")
      (node (ref "R26") (pin "R1B") (pinfunction "R1B_R1B") (pintype "passive"))
    )
    (net (code "104") (name "unconnected-(U$1-5-PadP$5)") (class "Default")
      (node (ref "U$1") (pin "P$5") (pinfunction "5_P$5") (pintype "bidirectional"))
    )
    (net (code "105") (name "unconnected-(U$1-6-PadP$6)") (class "Default")
      (node (ref "U$1") (pin "P$6") (pinfunction "6_P$6") (pintype "bidirectional"))
    )
    (net (code "106") (name "unconnected-(U$2-5-PadP$5)") (class "Default")
      (node (ref "U$2") (pin "P$5") (pinfunction "5_P$5") (pintype "bidirectional"))
    )
    (net (code "107") (name "unconnected-(U$2-6-PadP$6)") (class "Default")
      (node (ref "U$2") (pin "P$6") (pinfunction "6_P$6") (pintype "bidirectional"))
    )
    (net (code "108") (name "unconnected-(U$3-5-PadP$5)") (class "Default")
      (node (ref "U$3") (pin "P$5") (pinfunction "5_P$5") (pintype "bidirectional"))
    )
    (net (code "109") (name "unconnected-(U$3-6-PadP$6)") (class "Default")
      (node (ref "U$3") (pin "P$6") (pinfunction "6_P$6") (pintype "bidirectional"))
    )
    (net (code "110") (name "unconnected-(U$4-5-PadP$5)") (class "Default")
      (node (ref "U$4") (pin "P$5") (pinfunction "5_P$5") (pintype "bidirectional"))
    )
    (net (code "111") (name "unconnected-(U$4-6-PadP$6)") (class "Default")
      (node (ref "U$4") (pin "P$6") (pinfunction "6_P$6") (pintype "bidirectional"))
    )
    (net (code "112") (name "unconnected-(U$5-5-PadP$5)") (class "Default")
      (node (ref "U$5") (pin "P$5") (pinfunction "5_P$5") (pintype "bidirectional"))
    )
    (net (code "113") (name "unconnected-(U$5-6-PadP$6)") (class "Default")
      (node (ref "U$5") (pin "P$6") (pinfunction "6_P$6") (pintype "bidirectional"))
    )
    (net (code "114") (name "unconnected-(U$6-5-PadP$5)") (class "Default")
      (node (ref "U$6") (pin "P$5") (pinfunction "5_P$5") (pintype "bidirectional"))
    )
    (net (code "115") (name "unconnected-(U$6-6-PadP$6)") (class "Default")
      (node (ref "U$6") (pin "P$6") (pinfunction "6_P$6") (pintype "bidirectional"))
    )
    (net (code "116") (name "unconnected-(U$7-5-PadP$5)") (class "Default")
      (node (ref "U$7") (pin "P$5") (pinfunction "5_P$5") (pintype "bidirectional"))
    )
    (net (code "117") (name "unconnected-(U$7-6-PadP$6)") (class "Default")
      (node (ref "U$7") (pin "P$6") (pinfunction "6_P$6") (pintype "bidirectional"))
    )
    (net (code "118") (name "unconnected-(U$8-5-PadP$5)") (class "Default")
      (node (ref "U$8") (pin "P$5") (pinfunction "5_P$5") (pintype "bidirectional"))
    )
    (net (code "119") (name "unconnected-(U$8-6-PadP$6)") (class "Default")
      (node (ref "U$8") (pin "P$6") (pinfunction "6_P$6") (pintype "bidirectional"))
    )
    (net (code "120") (name "unconnected-(U3-RC13-PadP$47)") (class "Default")
      (node (ref "U3") (pin "P$47") (pinfunction "RC13_P$47") (pintype "bidirectional"))
    )
    (net (code "121") (name "unconnected-(U3-RC14-PadP$48)") (class "Default")
      (node (ref "U3") (pin "P$48") (pinfunction "RC14_P$48") (pintype "bidirectional"))
    )
    (net (code "122") (name "unconnected-(U3-RD1{slash}OC2-PadP$49)") (class "Default")
      (node (ref "U3") (pin "P$49") (pinfunction "RD1/OC2_P$49") (pintype "bidirectional"))
    )
    (net (code "123") (name "unconnected-(U3-RD8-PadP$42)") (class "Default")
      (node (ref "U3") (pin "P$42") (pinfunction "RD8_P$42") (pintype "bidirectional"))
    )
    (net (code "124") (name "unconnected-(U3-RD9-PadP$43)") (class "Default")
      (node (ref "U3") (pin "P$43") (pinfunction "RD9_P$43") (pintype "bidirectional"))
    )
    (net (code "125") (name "unconnected-(U3-RF4{slash}U2RX-PadP$31)") (class "Default")
      (node (ref "U3") (pin "P$31") (pinfunction "RF4/U2RX_P$31") (pintype "bidirectional"))
    )
    (net (code "126") (name "unconnected-(U25-PadP1)") (class "Default")
      (node (ref "U25") (pin "P1") (pinfunction "P1_P1") (pintype "bidirectional"))
    )
    (net (code "127") (name "unconnected-(U25-PadP2)") (class "Default")
      (node (ref "U25") (pin "P2") (pinfunction "P2_P2") (pintype "bidirectional"))
    )
    (net (code "128") (name "unconnected-(U25-PadP3)") (class "Default")
      (node (ref "U25") (pin "P3") (pinfunction "P3_P3") (pintype "bidirectional"))
    )
    (net (code "129") (name "unconnected-(U25-PadP4)") (class "Default")
      (node (ref "U25") (pin "P4") (pinfunction "P4_P4") (pintype "bidirectional"))
    )
    (net (code "130") (name "unconnected-(X1F-S-Pad6)") (class "Default")
      (node (ref "X1") (pin "6") (pinfunction "S_6") (pintype "passive"))
    )
    (net (code "131") (name "unconnected-(X2-SHIELD-PadP$4)") (class "Default")
      (node (ref "X2") (pin "P$4") (pinfunction "SHIELD_P$4") (pintype "bidirectional"))
    )
  )
)
